# Sheet1.net
KiCad netlist of a schematic drawn in Altium Designer
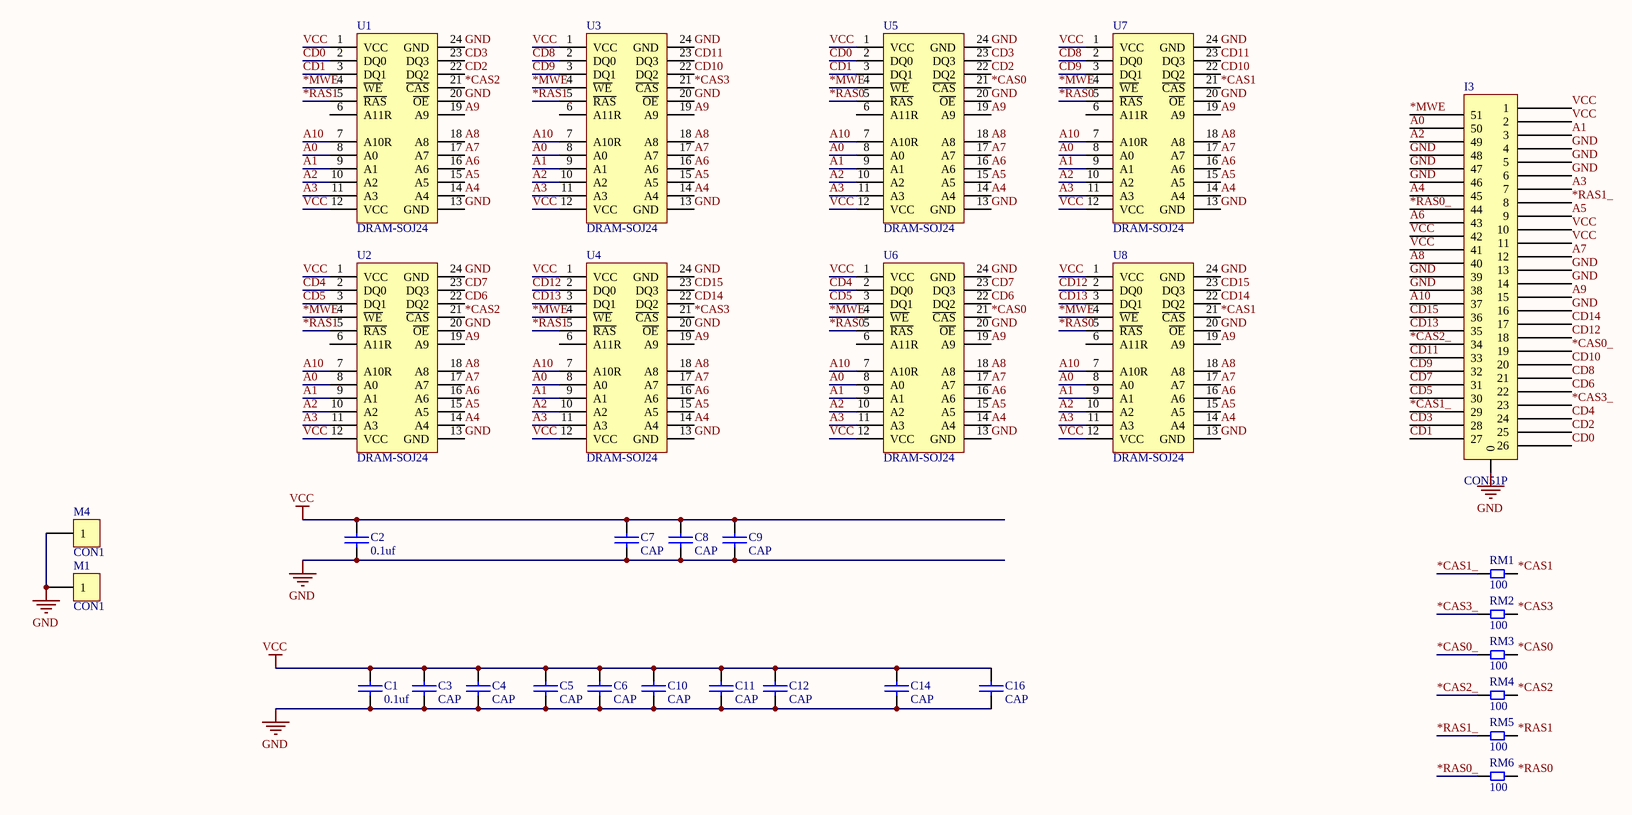
[diagram p0: Sheet1.SchDoc]

(export (version "E")
  (design (tool "Eeschema 10.0.6"))
  (components
    (comp (ref "C1") (value "0.1uf") (footprint "C0603") (libsource (lib "电阻电容二极管") (part "CAP")))
    (comp (ref "C2") (value "0.1uf") (footprint "C0603") (libsource (lib "电阻电容二极管") (part "CAP")))
    (comp (ref "C3") (value "CAP") (footprint "C0603") (libsource (lib "电阻电容二极管") (part "CAP")))
    (comp (ref "C4") (value "CAP") (footprint "C0603") (libsource (lib "电阻电容二极管") (part "CAP")))
    (comp (ref "C5") (value "CAP") (footprint "C0603") (libsource (lib "电阻电容二极管") (part "CAP")))
    (comp (ref "C6") (value "CAP") (footprint "C0603") (libsource (lib "电阻电容二极管") (part "CAP")))
    (comp (ref "C7") (value "CAP") (footprint "C0603") (libsource (lib "电阻电容二极管") (part "CAP")))
    (comp (ref "C8") (value "CAP") (footprint "C0603") (libsource (lib "电阻电容二极管") (part "CAP")))
    (comp (ref "C9") (value "CAP") (footprint "C0603") (libsource (lib "电阻电容二极管") (part "CAP")))
    (comp (ref "C10") (value "CAP") (footprint "C0603") (libsource (lib "电阻电容二极管") (part "CAP")))
    (comp (ref "C11") (value "CAP") (footprint "C0603") (libsource (lib "电阻电容二极管") (part "CAP")))
    (comp (ref "C12") (value "CAP") (footprint "C0603") (libsource (lib "电阻电容二极管") (part "CAP")))
    (comp (ref "C14") (value "CAP") (footprint "C0603") (libsource (lib "电阻电容二极管") (part "CAP")))
    (comp (ref "C16") (value "CAP") (footprint "C0603") (libsource (lib "电阻电容二极管") (part "CAP")))
    (comp (ref "I3") (value "CON51P") (footprint "BTB1.0-51P-b") (libsource (lib "常用元件库") (part "CON51P")))
    (comp (ref "M1") (value "CON1") (footprint "M2A") (libsource (lib "常用元件库") (part "CON1")))
    (comp (ref "M4") (value "CON1") (footprint "M2A") (libsource (lib "常用元件库") (part "CON1")))
    (comp (ref "RM1") (value "100") (footprint "R0603") (libsource (lib "电阻电容二极管") (part "RES2")))
    (comp (ref "RM2") (value "100") (footprint "R0603") (libsource (lib "电阻电容二极管") (part "RES2")))
    (comp (ref "RM3") (value "100") (footprint "R0603") (libsource (lib "电阻电容二极管") (part "RES2")))
    (comp (ref "RM4") (value "100") (footprint "R0603") (libsource (lib "电阻电容二极管") (part "RES2")))
    (comp (ref "RM5") (value "100") (footprint "R0603") (libsource (lib "电阻电容二极管") (part "RES2")))
    (comp (ref "RM6") (value "100") (footprint "R0603") (libsource (lib "电阻电容二极管") (part "RES2")))
    (comp (ref "U1") (value "DRAM-SOJ24") (footprint "SOJ-24-A") (libsource (lib "微机原理") (part "DRAM-SOJ24")))
    (comp (ref "U2") (value "DRAM-SOJ24") (footprint "SOJ-24-A") (libsource (lib "微机原理") (part "DRAM-SOJ24")))
    (comp (ref "U3") (value "DRAM-SOJ24") (footprint "SOJ-24-A") (libsource (lib "微机原理") (part "DRAM-SOJ24")))
    (comp (ref "U4") (value "DRAM-SOJ24") (footprint "SOJ-24-A") (libsource (lib "微机原理") (part "DRAM-SOJ24")))
    (comp (ref "U5") (value "DRAM-SOJ24") (footprint "SOJ-24-A") (libsource (lib "微机原理") (part "DRAM-SOJ24")))
    (comp (ref "U6") (value "DRAM-SOJ24") (footprint "SOJ-24-A") (libsource (lib "微机原理") (part "DRAM-SOJ24")))
    (comp (ref "U7") (value "DRAM-SOJ24") (footprint "SOJ-24-A") (libsource (lib "微机原理") (part "DRAM-SOJ24")))
    (comp (ref "U8") (value "DRAM-SOJ24") (footprint "SOJ-24-A") (libsource (lib "微机原理") (part "DRAM-SOJ24")))
  )
  (nets
    (net (code "1") (name "/*CAS0") (class "Default")
      (node (ref "RM3") (pin "2") (pinfunction "2_2") (pintype "passive"))
      (node (ref "U5") (pin "21") (pinfunction "~{CAS}_21") (pintype "passive"))
      (node (ref "U6") (pin "21") (pinfunction "~{CAS}_21") (pintype "passive"))
    )
    (net (code "2") (name "/*CAS0_") (class "Default")
      (node (ref "I3") (pin "19") (pinfunction "19_19") (pintype "passive"))
      (node (ref "RM3") (pin "1") (pinfunction "1_1") (pintype "passive"))
    )
    (net (code "3") (name "/*CAS1") (class "Default")
      (node (ref "RM1") (pin "2") (pinfunction "2_2") (pintype "passive"))
      (node (ref "U7") (pin "21") (pinfunction "~{CAS}_21") (pintype "passive"))
      (node (ref "U8") (pin "21") (pinfunction "~{CAS}_21") (pintype "passive"))
    )
    (net (code "4") (name "/*CAS1_") (class "Default")
      (node (ref "I3") (pin "29") (pinfunction "29_29") (pintype "passive"))
      (node (ref "RM1") (pin "1") (pinfunction "1_1") (pintype "passive"))
    )
    (net (code "5") (name "/*CAS2") (class "Default")
      (node (ref "RM4") (pin "2") (pinfunction "2_2") (pintype "passive"))
      (node (ref "U1") (pin "21") (pinfunction "~{CAS}_21") (pintype "passive"))
      (node (ref "U2") (pin "21") (pinfunction "~{CAS}_21") (pintype "passive"))
    )
    (net (code "6") (name "/*CAS2_") (class "Default")
      (node (ref "I3") (pin "34") (pinfunction "34_34") (pintype "passive"))
      (node (ref "RM4") (pin "1") (pinfunction "1_1") (pintype "passive"))
    )
    (net (code "7") (name "/*CAS3") (class "Default")
      (node (ref "RM2") (pin "2") (pinfunction "2_2") (pintype "passive"))
      (node (ref "U3") (pin "21") (pinfunction "~{CAS}_21") (pintype "passive"))
      (node (ref "U4") (pin "21") (pinfunction "~{CAS}_21") (pintype "passive"))
    )
    (net (code "8") (name "/*CAS3_") (class "Default")
      (node (ref "I3") (pin "23") (pinfunction "23_23") (pintype "passive"))
      (node (ref "RM2") (pin "1") (pinfunction "1_1") (pintype "passive"))
    )
    (net (code "9") (name "/*MWE") (class "Default")
      (node (ref "I3") (pin "51") (pinfunction "51_51") (pintype "passive"))
      (node (ref "U1") (pin "4") (pinfunction "~{WE}_4") (pintype "passive"))
      (node (ref "U2") (pin "4") (pinfunction "~{WE}_4") (pintype "passive"))
      (node (ref "U3") (pin "4") (pinfunction "~{WE}_4") (pintype "passive"))
      (node (ref "U4") (pin "4") (pinfunction "~{WE}_4") (pintype "passive"))
      (node (ref "U5") (pin "4") (pinfunction "~{WE}_4") (pintype "passive"))
      (node (ref "U6") (pin "4") (pinfunction "~{WE}_4") (pintype "passive"))
      (node (ref "U7") (pin "4") (pinfunction "~{WE}_4") (pintype "passive"))
      (node (ref "U8") (pin "4") (pinfunction "~{WE}_4") (pintype "passive"))
    )
    (net (code "10") (name "/*RAS0") (class "Default")
      (node (ref "RM6") (pin "2") (pinfunction "2_2") (pintype "passive"))
      (node (ref "U5") (pin "5") (pinfunction "~{RAS}_5") (pintype "passive"))
      (node (ref "U6") (pin "5") (pinfunction "~{RAS}_5") (pintype "passive"))
      (node (ref "U7") (pin "5") (pinfunction "~{RAS}_5") (pintype "passive"))
      (node (ref "U8") (pin "5") (pinfunction "~{RAS}_5") (pintype "passive"))
    )
    (net (code "11") (name "/*RAS0_") (class "Default")
      (node (ref "I3") (pin "44") (pinfunction "44_44") (pintype "passive"))
      (node (ref "RM6") (pin "1") (pinfunction "1_1") (pintype "passive"))
    )
    (net (code "12") (name "/*RAS1") (class "Default")
      (node (ref "RM5") (pin "2") (pinfunction "2_2") (pintype "passive"))
      (node (ref "U1") (pin "5") (pinfunction "~{RAS}_5") (pintype "passive"))
      (node (ref "U2") (pin "5") (pinfunction "~{RAS}_5") (pintype "passive"))
      (node (ref "U3") (pin "5") (pinfunction "~{RAS}_5") (pintype "passive"))
      (node (ref "U4") (pin "5") (pinfunction "~{RAS}_5") (pintype "passive"))
    )
    (net (code "13") (name "/*RAS1_") (class "Default")
      (node (ref "I3") (pin "8") (pinfunction "8_8") (pintype "passive"))
      (node (ref "RM5") (pin "1") (pinfunction "1_1") (pintype "passive"))
    )
    (net (code "14") (name "/A0") (class "Default")
      (node (ref "I3") (pin "50") (pinfunction "50_50") (pintype "passive"))
      (node (ref "U1") (pin "8") (pinfunction "A0_8") (pintype "passive"))
      (node (ref "U2") (pin "8") (pinfunction "A0_8") (pintype "passive"))
      (node (ref "U3") (pin "8") (pinfunction "A0_8") (pintype "passive"))
      (node (ref "U4") (pin "8") (pinfunction "A0_8") (pintype "passive"))
      (node (ref "U5") (pin "8") (pinfunction "A0_8") (pintype "passive"))
      (node (ref "U6") (pin "8") (pinfunction "A0_8") (pintype "passive"))
      (node (ref "U7") (pin "8") (pinfunction "A0_8") (pintype "passive"))
      (node (ref "U8") (pin "8") (pinfunction "A0_8") (pintype "passive"))
    )
    (net (code "15") (name "/A1") (class "Default")
      (node (ref "I3") (pin "3") (pinfunction "3_3") (pintype "passive"))
      (node (ref "U1") (pin "9") (pinfunction "A1_9") (pintype "passive"))
      (node (ref "U2") (pin "9") (pinfunction "A1_9") (pintype "passive"))
      (node (ref "U3") (pin "9") (pinfunction "A1_9") (pintype "passive"))
      (node (ref "U4") (pin "9") (pinfunction "A1_9") (pintype "passive"))
      (node (ref "U5") (pin "9") (pinfunction "A1_9") (pintype "passive"))
      (node (ref "U6") (pin "9") (pinfunction "A1_9") (pintype "passive"))
      (node (ref "U7") (pin "9") (pinfunction "A1_9") (pintype "passive"))
      (node (ref "U8") (pin "9") (pinfunction "A1_9") (pintype "passive"))
    )
    (net (code "16") (name "/A2") (class "Default")
      (node (ref "I3") (pin "49") (pinfunction "49_49") (pintype "passive"))
      (node (ref "U1") (pin "10") (pinfunction "A2_10") (pintype "passive"))
      (node (ref "U2") (pin "10") (pinfunction "A2_10") (pintype "passive"))
      (node (ref "U3") (pin "10") (pinfunction "A2_10") (pintype "passive"))
      (node (ref "U4") (pin "10") (pinfunction "A2_10") (pintype "passive"))
      (node (ref "U5") (pin "10") (pinfunction "A2_10") (pintype "passive"))
      (node (ref "U6") (pin "10") (pinfunction "A2_10") (pintype "passive"))
      (node (ref "U7") (pin "10") (pinfunction "A2_10") (pintype "passive"))
      (node (ref "U8") (pin "10") (pinfunction "A2_10") (pintype "passive"))
    )
    (net (code "17") (name "/A3") (class "Default")
      (node (ref "I3") (pin "7") (pinfunction "7_7") (pintype "passive"))
      (node (ref "U1") (pin "11") (pinfunction "A3_11") (pintype "passive"))
      (node (ref "U2") (pin "11") (pinfunction "A3_11") (pintype "passive"))
      (node (ref "U3") (pin "11") (pinfunction "A3_11") (pintype "passive"))
      (node (ref "U4") (pin "11") (pinfunction "A3_11") (pintype "passive"))
      (node (ref "U5") (pin "11") (pinfunction "A3_11") (pintype "passive"))
      (node (ref "U6") (pin "11") (pinfunction "A3_11") (pintype "passive"))
      (node (ref "U7") (pin "11") (pinfunction "A3_11") (pintype "passive"))
      (node (ref "U8") (pin "11") (pinfunction "A3_11") (pintype "passive"))
    )
    (net (code "18") (name "/A4") (class "Default")
      (node (ref "I3") (pin "45") (pinfunction "45_45") (pintype "passive"))
      (node (ref "U1") (pin "14") (pinfunction "A4_14") (pintype "passive"))
      (node (ref "U2") (pin "14") (pinfunction "A4_14") (pintype "passive"))
      (node (ref "U3") (pin "14") (pinfunction "A4_14") (pintype "passive"))
      (node (ref "U4") (pin "14") (pinfunction "A4_14") (pintype "passive"))
      (node (ref "U5") (pin "14") (pinfunction "A4_14") (pintype "passive"))
      (node (ref "U6") (pin "14") (pinfunction "A4_14") (pintype "passive"))
      (node (ref "U7") (pin "14") (pinfunction "A4_14") (pintype "passive"))
      (node (ref "U8") (pin "14") (pinfunction "A4_14") (pintype "passive"))
    )
    (net (code "19") (name "/A5") (class "Default")
      (node (ref "I3") (pin "9") (pinfunction "9_9") (pintype "passive"))
      (node (ref "U1") (pin "15") (pinfunction "A5_15") (pintype "passive"))
      (node (ref "U2") (pin "15") (pinfunction "A5_15") (pintype "passive"))
      (node (ref "U3") (pin "15") (pinfunction "A5_15") (pintype "passive"))
      (node (ref "U4") (pin "15") (pinfunction "A5_15") (pintype "passive"))
      (node (ref "U5") (pin "15") (pinfunction "A5_15") (pintype "passive"))
      (node (ref "U6") (pin "15") (pinfunction "A5_15") (pintype "passive"))
      (node (ref "U7") (pin "15") (pinfunction "A5_15") (pintype "passive"))
      (node (ref "U8") (pin "15") (pinfunction "A5_15") (pintype "passive"))
    )
    (net (code "20") (name "/A6") (class "Default")
      (node (ref "I3") (pin "43") (pinfunction "43_43") (pintype "passive"))
      (node (ref "U1") (pin "16") (pinfunction "A6_16") (pintype "passive"))
      (node (ref "U2") (pin "16") (pinfunction "A6_16") (pintype "passive"))
      (node (ref "U3") (pin "16") (pinfunction "A6_16") (pintype "passive"))
      (node (ref "U4") (pin "16") (pinfunction "A6_16") (pintype "passive"))
      (node (ref "U5") (pin "16") (pinfunction "A6_16") (pintype "passive"))
      (node (ref "U6") (pin "16") (pinfunction "A6_16") (pintype "passive"))
      (node (ref "U7") (pin "16") (pinfunction "A6_16") (pintype "passive"))
      (node (ref "U8") (pin "16") (pinfunction "A6_16") (pintype "passive"))
    )
    (net (code "21") (name "/A7") (class "Default")
      (node (ref "I3") (pin "12") (pinfunction "12_12") (pintype "passive"))
      (node (ref "U1") (pin "17") (pinfunction "A7_17") (pintype "passive"))
      (node (ref "U2") (pin "17") (pinfunction "A7_17") (pintype "passive"))
      (node (ref "U3") (pin "17") (pinfunction "A7_17") (pintype "passive"))
      (node (ref "U4") (pin "17") (pinfunction "A7_17") (pintype "passive"))
      (node (ref "U5") (pin "17") (pinfunction "A7_17") (pintype "passive"))
      (node (ref "U6") (pin "17") (pinfunction "A7_17") (pintype "passive"))
      (node (ref "U7") (pin "17") (pinfunction "A7_17") (pintype "passive"))
      (node (ref "U8") (pin "17") (pinfunction "A7_17") (pintype "passive"))
    )
    (net (code "22") (name "/A8") (class "Default")
      (node (ref "I3") (pin "40") (pinfunction "40_40") (pintype "passive"))
      (node (ref "U1") (pin "18") (pinfunction "A8_18") (pintype "passive"))
      (node (ref "U2") (pin "18") (pinfunction "A8_18") (pintype "passive"))
      (node (ref "U3") (pin "18") (pinfunction "A8_18") (pintype "passive"))
      (node (ref "U4") (pin "18") (pinfunction "A8_18") (pintype "passive"))
      (node (ref "U5") (pin "18") (pinfunction "A8_18") (pintype "passive"))
      (node (ref "U6") (pin "18") (pinfunction "A8_18") (pintype "passive"))
      (node (ref "U7") (pin "18") (pinfunction "A8_18") (pintype "passive"))
      (node (ref "U8") (pin "18") (pinfunction "A8_18") (pintype "passive"))
    )
    (net (code "23") (name "/A9") (class "Default")
      (node (ref "I3") (pin "15") (pinfunction "15_15") (pintype "passive"))
      (node (ref "U1") (pin "19") (pinfunction "A9_19") (pintype "passive"))
      (node (ref "U2") (pin "19") (pinfunction "A9_19") (pintype "passive"))
      (node (ref "U3") (pin "19") (pinfunction "A9_19") (pintype "passive"))
      (node (ref "U4") (pin "19") (pinfunction "A9_19") (pintype "passive"))
      (node (ref "U5") (pin "19") (pinfunction "A9_19") (pintype "passive"))
      (node (ref "U6") (pin "19") (pinfunction "A9_19") (pintype "passive"))
      (node (ref "U7") (pin "19") (pinfunction "A9_19") (pintype "passive"))
      (node (ref "U8") (pin "19") (pinfunction "A9_19") (pintype "passive"))
    )
    (net (code "24") (name "/A10") (class "Default")
      (node (ref "I3") (pin "37") (pinfunction "37_37") (pintype "passive"))
      (node (ref "U1") (pin "7") (pinfunction "A10R_7") (pintype "passive"))
      (node (ref "U2") (pin "7") (pinfunction "A10R_7") (pintype "passive"))
      (node (ref "U3") (pin "7") (pinfunction "A10R_7") (pintype "passive"))
      (node (ref "U4") (pin "7") (pinfunction "A10R_7") (pintype "passive"))
      (node (ref "U5") (pin "7") (pinfunction "A10R_7") (pintype "passive"))
      (node (ref "U6") (pin "7") (pinfunction "A10R_7") (pintype "passive"))
      (node (ref "U7") (pin "7") (pinfunction "A10R_7") (pintype "passive"))
      (node (ref "U8") (pin "7") (pinfunction "A10R_7") (pintype "passive"))
    )
    (net (code "25") (name "/CD0") (class "Default")
      (node (ref "I3") (pin "26") (pinfunction "26_26") (pintype "passive"))
      (node (ref "U1") (pin "2") (pinfunction "DQ0_2") (pintype "passive"))
      (node (ref "U5") (pin "2") (pinfunction "DQ0_2") (pintype "passive"))
    )
    (net (code "26") (name "/CD1") (class "Default")
      (node (ref "I3") (pin "27") (pinfunction "27_27") (pintype "passive"))
      (node (ref "U1") (pin "3") (pinfunction "DQ1_3") (pintype "passive"))
      (node (ref "U5") (pin "3") (pinfunction "DQ1_3") (pintype "passive"))
    )
    (net (code "27") (name "/CD2") (class "Default")
      (node (ref "I3") (pin "25") (pinfunction "25_25") (pintype "passive"))
      (node (ref "U1") (pin "22") (pinfunction "DQ2_22") (pintype "passive"))
      (node (ref "U5") (pin "22") (pinfunction "DQ2_22") (pintype "passive"))
    )
    (net (code "28") (name "/CD3") (class "Default")
      (node (ref "I3") (pin "28") (pinfunction "28_28") (pintype "passive"))
      (node (ref "U1") (pin "23") (pinfunction "DQ3_23") (pintype "passive"))
      (node (ref "U5") (pin "23") (pinfunction "DQ3_23") (pintype "passive"))
    )
    (net (code "29") (name "/CD4") (class "Default")
      (node (ref "I3") (pin "24") (pinfunction "24_24") (pintype "passive"))
      (node (ref "U2") (pin "2") (pinfunction "DQ0_2") (pintype "passive"))
      (node (ref "U6") (pin "2") (pinfunction "DQ0_2") (pintype "passive"))
    )
    (net (code "30") (name "/CD5") (class "Default")
      (node (ref "I3") (pin "30") (pinfunction "30_30") (pintype "passive"))
      (node (ref "U2") (pin "3") (pinfunction "DQ1_3") (pintype "passive"))
      (node (ref "U6") (pin "3") (pinfunction "DQ1_3") (pintype "passive"))
    )
    (net (code "31") (name "/CD6") (class "Default")
      (node (ref "I3") (pin "22") (pinfunction "22_22") (pintype "passive"))
      (node (ref "U2") (pin "22") (pinfunction "DQ2_22") (pintype "passive"))
      (node (ref "U6") (pin "22") (pinfunction "DQ2_22") (pintype "passive"))
    )
    (net (code "32") (name "/CD7") (class "Default")
      (node (ref "I3") (pin "31") (pinfunction "31_31") (pintype "passive"))
      (node (ref "U2") (pin "23") (pinfunction "DQ3_23") (pintype "passive"))
      (node (ref "U6") (pin "23") (pinfunction "DQ3_23") (pintype "passive"))
    )
    (net (code "33") (name "/CD8") (class "Default")
      (node (ref "I3") (pin "21") (pinfunction "21_21") (pintype "passive"))
      (node (ref "U3") (pin "2") (pinfunction "DQ0_2") (pintype "passive"))
      (node (ref "U7") (pin "2") (pinfunction "DQ0_2") (pintype "passive"))
    )
    (net (code "34") (name "/CD9") (class "Default")
      (node (ref "I3") (pin "32") (pinfunction "32_32") (pintype "passive"))
      (node (ref "U3") (pin "3") (pinfunction "DQ1_3") (pintype "passive"))
      (node (ref "U7") (pin "3") (pinfunction "DQ1_3") (pintype "passive"))
    )
    (net (code "35") (name "/CD10") (class "Default")
      (node (ref "I3") (pin "20") (pinfunction "20_20") (pintype "passive"))
      (node (ref "U3") (pin "22") (pinfunction "DQ2_22") (pintype "passive"))
      (node (ref "U7") (pin "22") (pinfunction "DQ2_22") (pintype "passive"))
    )
    (net (code "36") (name "/CD11") (class "Default")
      (node (ref "I3") (pin "33") (pinfunction "33_33") (pintype "passive"))
      (node (ref "U3") (pin "23") (pinfunction "DQ3_23") (pintype "passive"))
      (node (ref "U7") (pin "23") (pinfunction "DQ3_23") (pintype "passive"))
    )
    (net (code "37") (name "/CD12") (class "Default")
      (node (ref "I3") (pin "18") (pinfunction "18_18") (pintype "passive"))
      (node (ref "U4") (pin "2") (pinfunction "DQ0_2") (pintype "passive"))
      (node (ref "U8") (pin "2") (pinfunction "DQ0_2") (pintype "passive"))
    )
    (net (code "38") (name "/CD13") (class "Default")
      (node (ref "I3") (pin "35") (pinfunction "35_35") (pintype "passive"))
      (node (ref "U4") (pin "3") (pinfunction "DQ1_3") (pintype "passive"))
      (node (ref "U8") (pin "3") (pinfunction "DQ1_3") (pintype "passive"))
    )
    (net (code "39") (name "/CD14") (class "Default")
      (node (ref "I3") (pin "17") (pinfunction "17_17") (pintype "passive"))
      (node (ref "U4") (pin "22") (pinfunction "DQ2_22") (pintype "passive"))
      (node (ref "U8") (pin "22") (pinfunction "DQ2_22") (pintype "passive"))
    )
    (net (code "40") (name "/CD15") (class "Default")
      (node (ref "I3") (pin "36") (pinfunction "36_36") (pintype "passive"))
      (node (ref "U4") (pin "23") (pinfunction "DQ3_23") (pintype "passive"))
      (node (ref "U8") (pin "23") (pinfunction "DQ3_23") (pintype "passive"))
    )
    (net (code "41") (name "GND") (class "Default")
      (node (ref "C1") (pin "2") (pinfunction "2_2") (pintype "passive"))
      (node (ref "C10") (pin "2") (pinfunction "2_2") (pintype "passive"))
      (node (ref "C11") (pin "2") (pinfunction "2_2") (pintype "passive"))
      (node (ref "C12") (pin "2") (pinfunction "2_2") (pintype "passive"))
      (node (ref "C14") (pin "2") (pinfunction "2_2") (pintype "passive"))
      (node (ref "C16") (pin "2") (pinfunction "2_2") (pintype "passive"))
      (node (ref "C2") (pin "2") (pinfunction "2_2") (pintype "passive"))
      (node (ref "C3") (pin "2") (pinfunction "2_2") (pintype "passive"))
      (node (ref "C4") (pin "2") (pinfunction "2_2") (pintype "passive"))
      (node (ref "C5") (pin "2") (pinfunction "2_2") (pintype "passive"))
      (node (ref "C6") (pin "2") (pinfunction "2_2") (pintype "passive"))
      (node (ref "C7") (pin "2") (pinfunction "2_2") (pintype "passive"))
      (node (ref "C8") (pin "2") (pinfunction "2_2") (pintype "passive"))
      (node (ref "C9") (pin "2") (pinfunction "2_2") (pintype "passive"))
      (node (ref "I3") (pin "0") (pinfunction "0_0") (pintype "passive"))
      (node (ref "I3") (pin "13") (pinfunction "13_13") (pintype "passive"))
      (node (ref "I3") (pin "14") (pinfunction "14_14") (pintype "passive"))
      (node (ref "I3") (pin "16") (pinfunction "16_16") (pintype "passive"))
      (node (ref "I3") (pin "38") (pinfunction "38_38") (pintype "passive"))
      (node (ref "I3") (pin "39") (pinfunction "39_39") (pintype "passive"))
      (node (ref "I3") (pin "4") (pinfunction "4_4") (pintype "passive"))
      (node (ref "I3") (pin "46") (pinfunction "46_46") (pintype "passive"))
      (node (ref "I3") (pin "47") (pinfunction "47_47") (pintype "passive"))
      (node (ref "I3") (pin "48") (pinfunction "48_48") (pintype "passive"))
      (node (ref "I3") (pin "5") (pinfunction "5_5") (pintype "passive"))
      (node (ref "I3") (pin "6") (pinfunction "6_6") (pintype "passive"))
      (node (ref "M1") (pin "1") (pinfunction "1_1") (pintype "passive"))
      (node (ref "M4") (pin "1") (pinfunction "1_1") (pintype "passive"))
      (node (ref "U1") (pin "13") (pinfunction "GND_13") (pintype "passive"))
      (node (ref "U1") (pin "20") (pinfunction "~{OE}_20") (pintype "passive"))
      (node (ref "U1") (pin "24") (pinfunction "GND_24") (pintype "passive"))
      (node (ref "U2") (pin "13") (pinfunction "GND_13") (pintype "passive"))
      (node (ref "U2") (pin "20") (pinfunction "~{OE}_20") (pintype "passive"))
      (node (ref "U2") (pin "24") (pinfunction "GND_24") (pintype "passive"))
      (node (ref "U3") (pin "13") (pinfunction "GND_13") (pintype "passive"))
      (node (ref "U3") (pin "20") (pinfunction "~{OE}_20") (pintype "passive"))
      (node (ref "U3") (pin "24") (pinfunction "GND_24") (pintype "passive"))
      (node (ref "U4") (pin "13") (pinfunction "GND_13") (pintype "passive"))
      (node (ref "U4") (pin "20") (pinfunction "~{OE}_20") (pintype "passive"))
      (node (ref "U4") (pin "24") (pinfunction "GND_24") (pintype "passive"))
      (node (ref "U5") (pin "13") (pinfunction "GND_13") (pintype "passive"))
      (node (ref "U5") (pin "20") (pinfunction "~{OE}_20") (pintype "passive"))
      (node (ref "U5") (pin "24") (pinfunction "GND_24") (pintype "passive"))
      (node (ref "U6") (pin "13") (pinfunction "GND_13") (pintype "passive"))
      (node (ref "U6") (pin "20") (pinfunction "~{OE}_20") (pintype "passive"))
      (node (ref "U6") (pin "24") (pinfunction "GND_24") (pintype "passive"))
      (node (ref "U7") (pin "13") (pinfunction "GND_13") (pintype "passive"))
      (node (ref "U7") (pin "20") (pinfunction "~{OE}_20") (pintype "passive"))
      (node (ref "U7") (pin "24") (pinfunction "GND_24") (pintype "passive"))
      (node (ref "U8") (pin "13") (pinfunction "GND_13") (pintype "passive"))
      (node (ref "U8") (pin "20") (pinfunction "~{OE}_20") (pintype "passive"))
      (node (ref "U8") (pin "24") (pinfunction "GND_24") (pintype "passive"))
    )
    (net (code "42") (name "VCC") (class "Default")
      (node (ref "C1") (pin "1") (pinfunction "1_1") (pintype "passive"))
      (node (ref "C10") (pin "1") (pinfunction "1_1") (pintype "passive"))
      (node (ref "C11") (pin "1") (pinfunction "1_1") (pintype "passive"))
      (node (ref "C12") (pin "1") (pinfunction "1_1") (pintype "passive"))
      (node (ref "C14") (pin "1") (pinfunction "1_1") (pintype "passive"))
      (node (ref "C16") (pin "1") (pinfunction "1_1") (pintype "passive"))
      (node (ref "C2") (pin "1") (pinfunction "1_1") (pintype "passive"))
      (node (ref "C3") (pin "1") (pinfunction "1_1") (pintype "passive"))
      (node (ref "C4") (pin "1") (pinfunction "1_1") (pintype "passive"))
      (node (ref "C5") (pin "1") (pinfunction "1_1") (pintype "passive"))
      (node (ref "C6") (pin "1") (pinfunction "1_1") (pintype "passive"))
      (node (ref "C7") (pin "1") (pinfunction "1_1") (pintype "passive"))
      (node (ref "C8") (pin "1") (pinfunction "1_1") (pintype "passive"))
      (node (ref "C9") (pin "1") (pinfunction "1_1") (pintype "passive"))
      (node (ref "I3") (pin "1") (pinfunction "1_1") (pintype "passive"))
      (node (ref "I3") (pin "10") (pinfunction "10_10") (pintype "passive"))
      (node (ref "I3") (pin "11") (pinfunction "11_11") (pintype "passive"))
      (node (ref "I3") (pin "2") (pinfunction "2_2") (pintype "passive"))
      (node (ref "I3") (pin "41") (pinfunction "41_41") (pintype "passive"))
      (node (ref "I3") (pin "42") (pinfunction "42_42") (pintype "passive"))
      (node (ref "U1") (pin "1") (pinfunction "VCC_1") (pintype "passive"))
      (node (ref "U1") (pin "12") (pinfunction "VCC_12") (pintype "passive"))
      (node (ref "U2") (pin "1") (pinfunction "VCC_1") (pintype "passive"))
      (node (ref "U2") (pin "12") (pinfunction "VCC_12") (pintype "passive"))
      (node (ref "U3") (pin "1") (pinfunction "VCC_1") (pintype "passive"))
      (node (ref "U3") (pin "12") (pinfunction "VCC_12") (pintype "passive"))
      (node (ref "U4") (pin "1") (pinfunction "VCC_1") (pintype "passive"))
      (node (ref "U4") (pin "12") (pinfunction "VCC_12") (pintype "passive"))
      (node (ref "U5") (pin "1") (pinfunction "VCC_1") (pintype "passive"))
      (node (ref "U5") (pin "12") (pinfunction "VCC_12") (pintype "passive"))
      (node (ref "U6") (pin "1") (pinfunction "VCC_1") (pintype "passive"))
      (node (ref "U6") (pin "12") (pinfunction "VCC_12") (pintype "passive"))
      (node (ref "U7") (pin "1") (pinfunction "VCC_1") (pintype "passive"))
      (node (ref "U7") (pin "12") (pinfunction "VCC_12") (pintype "passive"))
      (node (ref "U8") (pin "1") (pinfunction "VCC_1") (pintype "passive"))
      (node (ref "U8") (pin "12") (pinfunction "VCC_12") (pintype "passive"))
    )
    (net (code "43") (name "unconnected-(U1-A11R-Pad6)") (class "Default")
      (node (ref "U1") (pin "6") (pinfunction "A11R_6") (pintype "passive"))
    )
    (net (code "44") (name "unconnected-(U2-A11R-Pad6)") (class "Default")
      (node (ref "U2") (pin "6") (pinfunction "A11R_6") (pintype "passive"))
    )
    (net (code "45") (name "unconnected-(U3-A11R-Pad6)") (class "Default")
      (node (ref "U3") (pin "6") (pinfunction "A11R_6") (pintype "passive"))
    )
    (net (code "46") (name "unconnected-(U4-A11R-Pad6)") (class "Default")
      (node (ref "U4") (pin "6") (pinfunction "A11R_6") (pintype "passive"))
    )
    (net (code "47") (name "unconnected-(U5-A11R-Pad6)") (class "Default")
      (node (ref "U5") (pin "6") (pinfunction "A11R_6") (pintype "passive"))
    )
    (net (code "48") (name "unconnected-(U6-A11R-Pad6)") (class "Default")
      (node (ref "U6") (pin "6") (pinfunction "A11R_6") (pintype "passive"))
    )
    (net (code "49") (name "unconnected-(U7-A11R-Pad6)") (class "Default")
      (node (ref "U7") (pin "6") (pinfunction "A11R_6") (pintype "passive"))
    )
    (net (code "50") (name "unconnected-(U8-A11R-Pad6)") (class "Default")
      (node (ref "U8") (pin "6") (pinfunction "A11R_6") (pintype "passive"))
    )
  )
)
